# RCShield-arm-v0.net
KiCad netlist of a schematic drawn in EAGLE
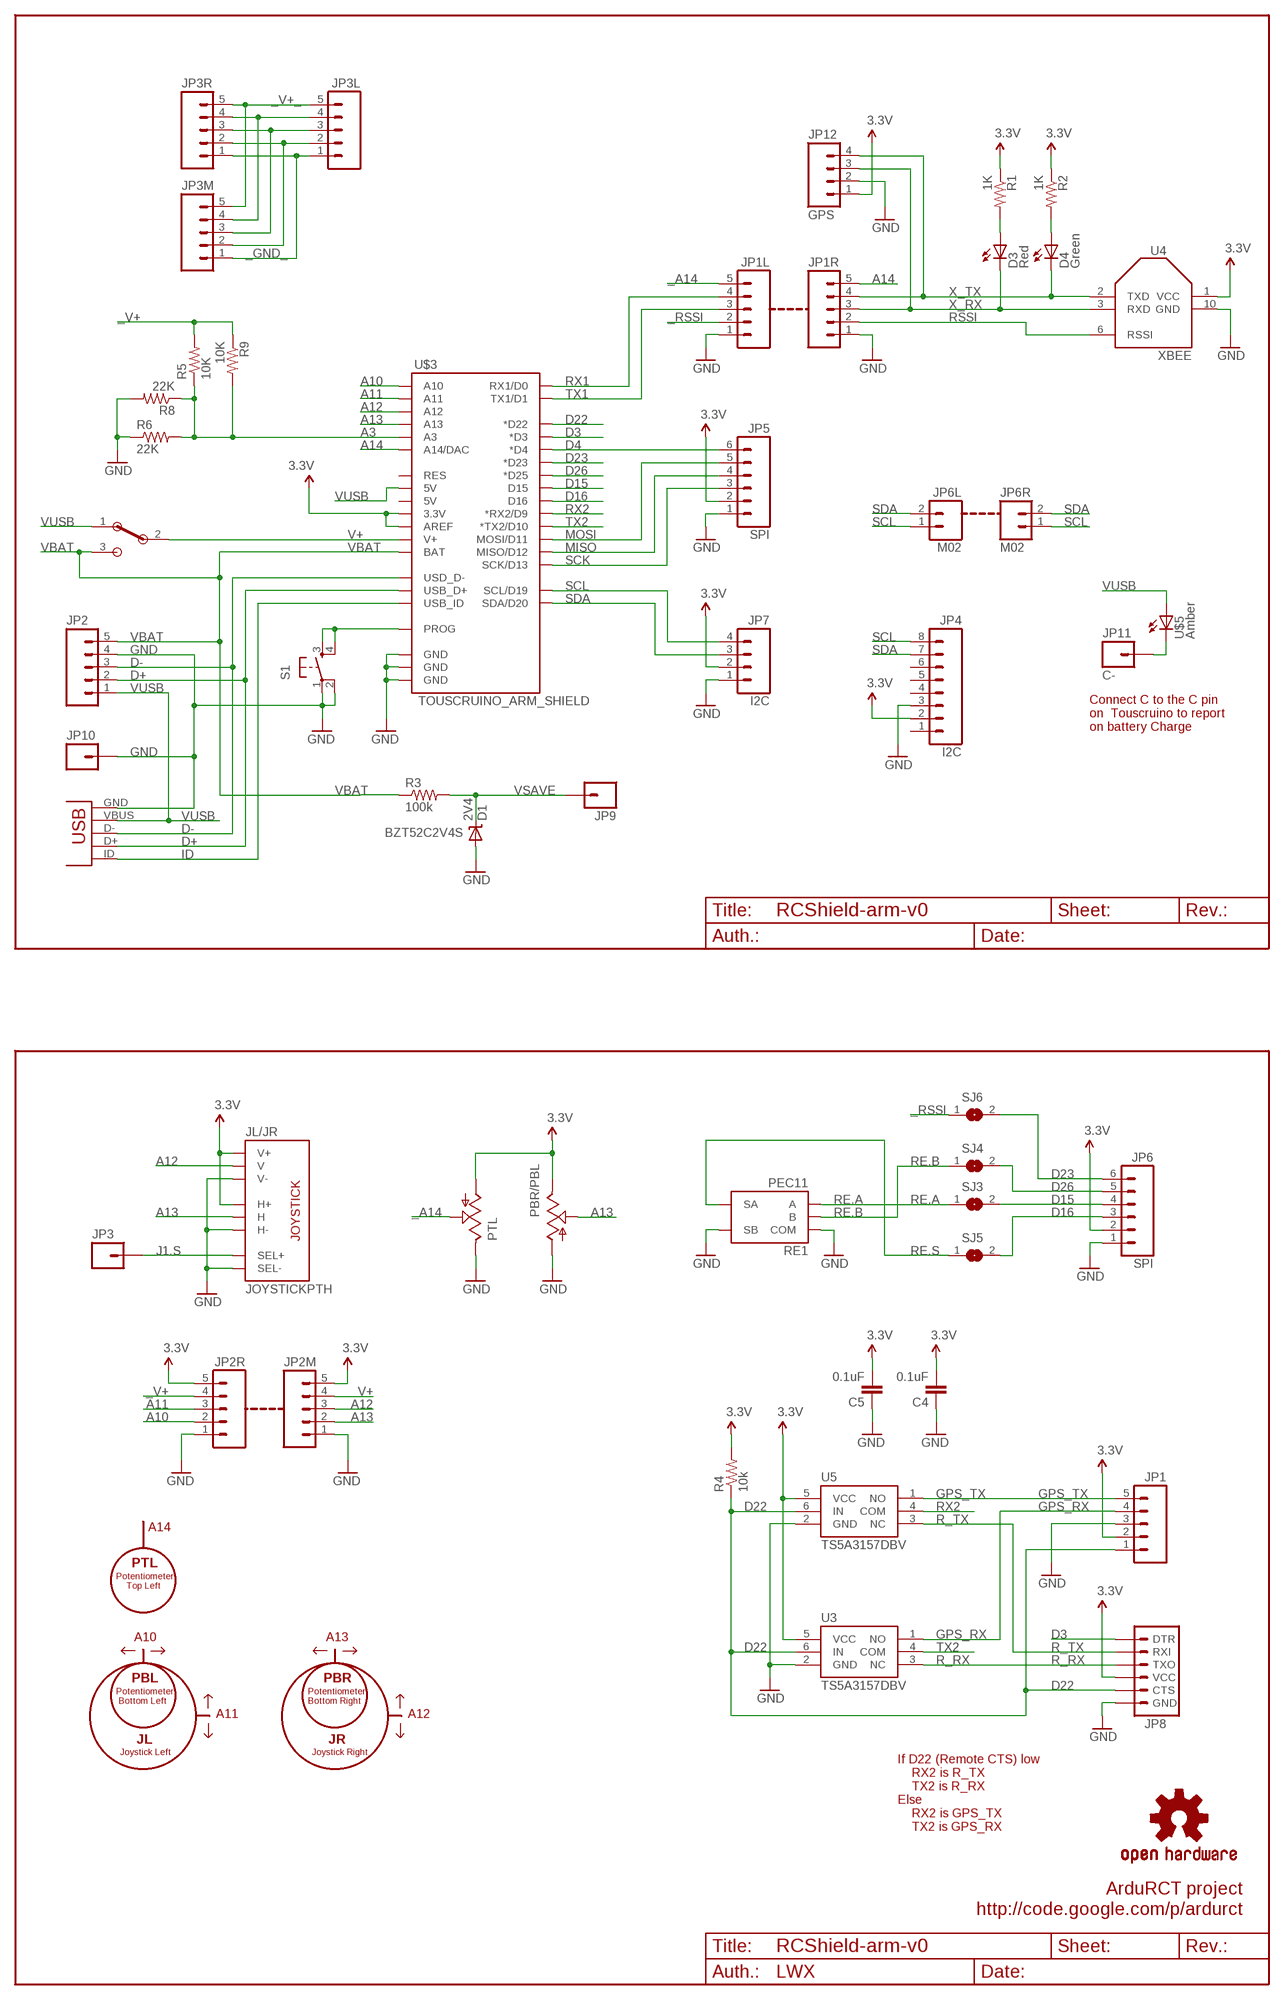
[diagram p0: schematic, sheet 1]

(export (version "E")
  (design (tool "Eeschema 10.0.6"))
  (components
    (comp (ref "C4")
      (value "0.1uF")
      (footprint "eagle-import:0805")
      (libsource (lib "eagle-import") (part "CAP0805"))
    )
    (comp (ref "C5")
      (value "0.1uF")
      (footprint "eagle-import:0805")
      (libsource (lib "eagle-import") (part "CAP0805"))
    )
    (comp (ref "D1")
      (value "2V4")
      (footprint "eagle-import:SOD-323")
      (libsource (lib "eagle-import") (part "DIODE-ZENER-BZT52"))
    )
    (comp (ref "D3")
      (value "Red")
      (footprint "eagle-import:LED")
      (libsource (lib "eagle-import") (part "LED"))
    )
    (comp (ref "D4")
      (value "Green")
      (footprint "eagle-import:LED")
      (libsource (lib "eagle-import") (part "LED"))
    )
    (comp (ref "JL/JR")
      (value "JOYSTICKPTH")
      (footprint "eagle-import:JOYSTICK")
      (libsource (lib "eagle-import") (part "JOYSTICKPTH"))
    )
    (comp (ref "JP1")
      (value "M05PTH")
      (footprint "eagle-import:1X05")
      (libsource (lib "eagle-import") (part "M05PTH"))
    )
    (comp (ref "JP1L")
      (value "M05")
      (footprint "eagle-import:2+3")
      (libsource (lib "eagle-import") (part "M05"))
    )
    (comp (ref "JP1R")
      (value "M05")
      (footprint "eagle-import:2+3")
      (libsource (lib "eagle-import") (part "M05"))
    )
    (comp (ref "JP2")
      (value "M05PTH")
      (footprint "eagle-import:1X05")
      (libsource (lib "eagle-import") (part "M05PTH"))
    )
    (comp (ref "JP2M")
      (value "M05")
      (footprint "eagle-import:2+3")
      (libsource (lib "eagle-import") (part "M05"))
    )
    (comp (ref "JP2R")
      (value "M05")
      (footprint "eagle-import:2+3")
      (libsource (lib "eagle-import") (part "M05"))
    )
    (comp (ref "JP3")
      (value "M01PTH")
      (footprint "eagle-import:1X01")
      (libsource (lib "eagle-import") (part "M01PTH"))
    )
    (comp (ref "JP3L")
      (value "M05")
      (footprint "eagle-import:2+3")
      (libsource (lib "eagle-import") (part "M05"))
    )
    (comp (ref "JP3M")
      (value "M05")
      (footprint "eagle-import:2+3")
      (libsource (lib "eagle-import") (part "M05"))
    )
    (comp (ref "JP3R")
      (value "M05")
      (footprint "eagle-import:2+3")
      (libsource (lib "eagle-import") (part "M05"))
    )
    (comp (ref "JP4")
      (value "I2C")
      (footprint "eagle-import:1X08")
      (libsource (lib "eagle-import") (part "M08"))
    )
    (comp (ref "JP5")
      (value "SPI")
      (footprint "eagle-import:1X06")
      (libsource (lib "eagle-import") (part "M06SIP"))
    )
    (comp (ref "JP6")
      (value "SPI")
      (footprint "eagle-import:1X06")
      (libsource (lib "eagle-import") (part "M06SIP"))
    )
    (comp (ref "JP6L")
      (value "M02")
      (footprint "eagle-import:1X02")
      (libsource (lib "eagle-import") (part "M02"))
    )
    (comp (ref "JP6R")
      (value "M02")
      (footprint "eagle-import:1X02")
      (libsource (lib "eagle-import") (part "M02"))
    )
    (comp (ref "JP7")
      (value "I2C")
      (footprint "eagle-import:1X04")
      (libsource (lib "eagle-import") (part "M04"))
    )
    (comp (ref "JP8")
      (value "ARDUINO_SERIAL_PROGRAM")
      (footprint "eagle-import:1X06_F")
      (libsource (lib "eagle-import") (part "ARDUINO_SERIAL_PROGRAM"))
    )
    (comp (ref "JP9")
      (value "M01PTH")
      (footprint "eagle-import:1X01")
      (libsource (lib "eagle-import") (part "M01PTH"))
    )
    (comp (ref "JP10")
      (value "M01PTH")
      (footprint "eagle-import:1X01")
      (libsource (lib "eagle-import") (part "M01PTH"))
    )
    (comp (ref "JP11")
      (value "C-")
      (footprint "eagle-import:1X01")
      (libsource (lib "eagle-import") (part "M01PTH"))
    )
    (comp (ref "JP12")
      (value "GPS")
      (footprint "eagle-import:1X04")
      (libsource (lib "eagle-import") (part "M04"))
    )
    (comp (ref "PBR/PBL")
      (value "POT")
      (footprint "eagle-import:ALPS_POT")
      (libsource (lib "eagle-import") (part "POT"))
    )
    (comp (ref "PTL")
      (value "POT")
      (footprint "eagle-import:ALPS_POT")
      (libsource (lib "eagle-import") (part "POT"))
    )
    (comp (ref "R1")
      (value "1K")
      (footprint "eagle-import:0805")
      (libsource (lib "eagle-import") (part "RESISTOR0805-RES"))
    )
    (comp (ref "R2")
      (value "1K")
      (footprint "eagle-import:0805")
      (libsource (lib "eagle-import") (part "RESISTOR0805-RES"))
    )
    (comp (ref "R3")
      (value "100k")
      (footprint "eagle-import:0805")
      (libsource (lib "eagle-import") (part "RESISTOR0805-RES"))
    )
    (comp (ref "R4")
      (value "10k")
      (footprint "eagle-import:0805")
      (libsource (lib "eagle-import") (part "RESISTOR0805-RES"))
    )
    (comp (ref "R5")
      (value "10K")
      (footprint "eagle-import:0805")
      (libsource (lib "eagle-import") (part "RESISTOR0805-RES"))
    )
    (comp (ref "R6")
      (value "22K")
      (footprint "eagle-import:0805")
      (libsource (lib "eagle-import") (part "RESISTOR0805-RES"))
    )
    (comp (ref "R8")
      (value "22K")
      (footprint "eagle-import:0207_7")
      (libsource (lib "eagle-import") (part "R-US_0207/7"))
    )
    (comp (ref "R9")
      (value "10K")
      (footprint "eagle-import:0207_7")
      (libsource (lib "eagle-import") (part "R-US_0207/7"))
    )
    (comp (ref "RE1")
      (value "PEC11")
      (footprint "eagle-import:PEC11")
      (libsource (lib "eagle-import") (part "PEC11"))
    )
    (comp (ref "S1")
      (value "TAC_SWITCHPTH")
      (footprint "eagle-import:TACTILE-PTH")
      (libsource (lib "eagle-import") (part "TAC_SWITCHPTH"))
    )
    (comp (ref "S4")
      (value "EG1224")
      (footprint "eagle-import:EG1224")
      (libsource (lib "eagle-import") (part "EG1224"))
    )
    (comp (ref "SJ3") (value "SJ") (footprint "eagle-import:SJ") (libsource (lib "eagle-import") (part "SJ")))
    (comp (ref "SJ4") (value "SJ") (footprint "eagle-import:SJ") (libsource (lib "eagle-import") (part "SJ")))
    (comp (ref "SJ5") (value "SJ") (footprint "eagle-import:SJ") (libsource (lib "eagle-import") (part "SJ")))
    (comp (ref "SJ6") (value "SJ") (footprint "eagle-import:SJ") (libsource (lib "eagle-import") (part "SJ")))
    (comp (ref "U$1")
      (value "OSHW-LOGOM")
      (footprint "eagle-import:OSHW-LOGO-M")
      (libsource (lib "eagle-import") (part "OSHW-LOGOM"))
    )
    (comp (ref "U$3")
      (value "TOUSCRUINO_ARM_SHIELD")
      (footprint "eagle-import:TOUSCRUINO_ARM_SHIELD_SPLIT")
      (libsource (lib "eagle-import") (part "TOUSCRUINO_ARM_SHIELD"))
    )
    (comp (ref "U$5")
      (value "Amber")
      (footprint "eagle-import:LED")
      (libsource (lib "eagle-import") (part "LED"))
    )
    (comp (ref "U3")
      (value "TS5A3157DBV")
      (footprint "eagle-import:SOT23-6")
      (libsource (lib "eagle-import") (part "TS5A3157DBV"))
    )
    (comp (ref "U4")
      (value "XBEE")
      (footprint "eagle-import:XBEE-SMD")
      (libsource (lib "eagle-import") (part "XBEE-RSSI"))
    )
    (comp (ref "U5")
      (value "TS5A3157DBV")
      (footprint "eagle-import:SOT23-6")
      (libsource (lib "eagle-import") (part "TS5A3157DBV"))
    )
    (comp (ref "X1")
      (value "USB")
      (footprint "eagle-import:USB-MICROB")
      (libsource (lib "eagle-import") (part "USB"))
    )
  )
  (nets
    (net (code "1") (name "/A3") (class "Default")
      (node (ref "R5") (pin "1") (pinfunction "1_1") (pintype "passive"))
      (node (ref "R6") (pin "2") (pinfunction "2_2") (pintype "passive"))
      (node (ref "R8") (pin "1") (pinfunction "1_1") (pintype "passive"))
      (node (ref "R9") (pin "2") (pinfunction "2_2") (pintype "passive"))
      (node (ref "U$3") (pin "A3") (pinfunction "A3_A3") (pintype "bidirectional"))
    )
    (net (code "2") (name "/A10") (class "Default")
      (node (ref "JP2R") (pin "2") (pinfunction "2_2") (pintype "passive"))
      (node (ref "U$3") (pin "A10") (pinfunction "A10_A10") (pintype "bidirectional"))
    )
    (net (code "3") (name "/A11") (class "Default")
      (node (ref "JP2R") (pin "3") (pinfunction "3_3") (pintype "passive"))
      (node (ref "U$3") (pin "A11") (pinfunction "A11_A11") (pintype "bidirectional"))
    )
    (net (code "4") (name "/A12") (class "Default")
      (node (ref "JL/JR") (pin "V2") (pinfunction "V_V2") (pintype "bidirectional"))
      (node (ref "JP2M") (pin "3") (pinfunction "3_3") (pintype "passive"))
      (node (ref "U$3") (pin "A12") (pinfunction "A12_A12") (pintype "bidirectional"))
    )
    (net (code "5") (name "/A13") (class "Default")
      (node (ref "JL/JR") (pin "H2") (pinfunction "H_H2") (pintype "bidirectional"))
      (node (ref "JP2M") (pin "2") (pinfunction "2_2") (pintype "passive"))
      (node (ref "PBR/PBL") (pin "P$2") (pinfunction "S_P$2") (pintype "passive"))
      (node (ref "U$3") (pin "A13") (pinfunction "A13_A13") (pintype "bidirectional"))
    )
    (net (code "6") (name "/A14") (class "Default")
      (node (ref "JP1R") (pin "5") (pinfunction "5_5") (pintype "passive"))
      (node (ref "U$3") (pin "A14") (pinfunction "A14/DAC_A14") (pintype "bidirectional"))
    )
    (net (code "7") (name "/D+") (class "Default")
      (node (ref "JP2") (pin "2") (pinfunction "2_2") (pintype "passive"))
      (node (ref "U$3") (pin "USB_D+") (pinfunction "USB_D+_USB_D+") (pintype "bidirectional"))
      (node (ref "X1") (pin "D+") (pinfunction "D+_D+") (pintype "bidirectional"))
    )
    (net (code "8") (name "/D-") (class "Default")
      (node (ref "JP2") (pin "3") (pinfunction "3_3") (pintype "passive"))
      (node (ref "U$3") (pin "USB_D-") (pinfunction "USD_D-_USB_D-") (pintype "bidirectional"))
      (node (ref "X1") (pin "D-") (pinfunction "D-_D-") (pintype "bidirectional"))
    )
    (net (code "9") (name "/D3") (class "Default")
      (node (ref "JP8") (pin "1") (pinfunction "DTR_1") (pintype "passive"))
      (node (ref "U$3") (pin "D3") (pinfunction "*D3_D3") (pintype "bidirectional"))
    )
    (net (code "10") (name "/D4") (class "Default")
      (node (ref "JP5") (pin "6") (pinfunction "6_6") (pintype "passive"))
      (node (ref "U$3") (pin "D4") (pinfunction "*D4_D4") (pintype "bidirectional"))
    )
    (net (code "11") (name "/D15") (class "Default")
      (node (ref "JP6") (pin "4") (pinfunction "4_4") (pintype "passive"))
      (node (ref "SJ3") (pin "2") (pinfunction "2_2") (pintype "passive"))
      (node (ref "U$3") (pin "D15") (pinfunction "D15_D15") (pintype "bidirectional"))
    )
    (net (code "12") (name "/D16") (class "Default")
      (node (ref "JP6") (pin "3") (pinfunction "3_3") (pintype "passive"))
      (node (ref "SJ5") (pin "2") (pinfunction "2_2") (pintype "passive"))
      (node (ref "U$3") (pin "D16") (pinfunction "D16_D16") (pintype "bidirectional"))
    )
    (net (code "13") (name "/D22") (class "Default")
      (node (ref "JP1") (pin "1") (pinfunction "1_1") (pintype "passive"))
      (node (ref "JP8") (pin "5") (pinfunction "CTS_5") (pintype "passive"))
      (node (ref "R4") (pin "1") (pinfunction "1_1") (pintype "passive"))
      (node (ref "U$3") (pin "D22") (pinfunction "*D22_D22") (pintype "bidirectional"))
      (node (ref "U3") (pin "6") (pinfunction "IN_6") (pintype "bidirectional"))
      (node (ref "U5") (pin "6") (pinfunction "IN_6") (pintype "bidirectional"))
    )
    (net (code "14") (name "/D23") (class "Default")
      (node (ref "JP6") (pin "6") (pinfunction "6_6") (pintype "passive"))
      (node (ref "SJ6") (pin "2") (pinfunction "2_2") (pintype "passive"))
      (node (ref "U$3") (pin "D23") (pinfunction "*D23_D23") (pintype "bidirectional"))
    )
    (net (code "15") (name "/D26") (class "Default")
      (node (ref "JP6") (pin "5") (pinfunction "5_5") (pintype "passive"))
      (node (ref "SJ4") (pin "2") (pinfunction "2_2") (pintype "passive"))
      (node (ref "U$3") (pin "D25") (pinfunction "*D25_D25") (pintype "bidirectional"))
    )
    (net (code "16") (name "/GPS_RX") (class "Default")
      (node (ref "JP1") (pin "4") (pinfunction "4_4") (pintype "passive"))
      (node (ref "U3") (pin "1") (pinfunction "NO_1") (pintype "bidirectional"))
    )
    (net (code "17") (name "/GPS_TX") (class "Default")
      (node (ref "JP1") (pin "5") (pinfunction "5_5") (pintype "passive"))
      (node (ref "U5") (pin "1") (pinfunction "NO_1") (pintype "bidirectional"))
    )
    (net (code "18") (name "/ID") (class "Default")
      (node (ref "U$3") (pin "USB_ID") (pinfunction "USB_ID_USB_ID") (pintype "bidirectional"))
      (node (ref "X1") (pin "ID") (pinfunction "ID_ID") (pintype "bidirectional"))
    )
    (net (code "19") (name "/J1.S") (class "Default")
      (node (ref "JL/JR") (pin "B1A") (pinfunction "SEL+_B1A") (pintype "bidirectional"))
      (node (ref "JP3") (pin "1") (pinfunction "1_1") (pintype "passive"))
    )
    (net (code "20") (name "/MISO") (class "Default")
      (node (ref "JP5") (pin "4") (pinfunction "4_4") (pintype "passive"))
      (node (ref "U$3") (pin "D12") (pinfunction "MISO/D12_D12") (pintype "bidirectional"))
    )
    (net (code "21") (name "/MOSI") (class "Default")
      (node (ref "JP5") (pin "5") (pinfunction "5_5") (pintype "passive"))
      (node (ref "U$3") (pin "D11") (pinfunction "MOSI/D11_D11") (pintype "bidirectional"))
    )
    (net (code "22") (name "/RE.A") (class "Default")
      (node (ref "RE1") (pin "A") (pinfunction "A_A") (pintype "bidirectional"))
      (node (ref "SJ3") (pin "1") (pinfunction "1_1") (pintype "passive"))
    )
    (net (code "23") (name "/RE.B") (class "Default")
      (node (ref "RE1") (pin "B") (pinfunction "B_B") (pintype "bidirectional"))
      (node (ref "SJ4") (pin "1") (pinfunction "1_1") (pintype "passive"))
    )
    (net (code "24") (name "/RE.S") (class "Default")
      (node (ref "RE1") (pin "S1") (pinfunction "SA_S1") (pintype "bidirectional"))
      (node (ref "SJ5") (pin "1") (pinfunction "1_1") (pintype "passive"))
    )
    (net (code "25") (name "/RSSI") (class "Default")
      (node (ref "JP1R") (pin "2") (pinfunction "2_2") (pintype "passive"))
      (node (ref "U4") (pin "6") (pinfunction "RSSI_6") (pintype "bidirectional"))
    )
    (net (code "26") (name "/RX1") (class "Default")
      (node (ref "JP1L") (pin "4") (pinfunction "4_4") (pintype "passive"))
      (node (ref "U$3") (pin "RX1/D0") (pinfunction "RX1/D0_RX1/D0") (pintype "bidirectional"))
    )
    (net (code "27") (name "/RX2") (class "Default")
      (node (ref "U$3") (pin "D9") (pinfunction "*RX2/D9_D9") (pintype "bidirectional"))
      (node (ref "U5") (pin "4") (pinfunction "COM_4") (pintype "bidirectional"))
    )
    (net (code "28") (name "/R_RX") (class "Default")
      (node (ref "JP8") (pin "3") (pinfunction "TXO_3") (pintype "passive"))
      (node (ref "U3") (pin "3") (pinfunction "NC_3") (pintype "bidirectional"))
    )
    (net (code "29") (name "/R_TX") (class "Default")
      (node (ref "JP8") (pin "2") (pinfunction "RXI_2") (pintype "passive"))
      (node (ref "U5") (pin "3") (pinfunction "NC_3") (pintype "bidirectional"))
    )
    (net (code "30") (name "/SCK") (class "Default")
      (node (ref "JP5") (pin "3") (pinfunction "3_3") (pintype "passive"))
      (node (ref "U$3") (pin "D13") (pinfunction "SCK/D13_D13") (pintype "bidirectional"))
    )
    (net (code "31") (name "/SCL") (class "Default")
      (node (ref "JP4") (pin "8") (pinfunction "8_8") (pintype "passive"))
      (node (ref "JP6L") (pin "1") (pinfunction "1_1") (pintype "passive"))
      (node (ref "JP6R") (pin "1") (pinfunction "1_1") (pintype "passive"))
      (node (ref "JP7") (pin "4") (pinfunction "4_4") (pintype "passive"))
      (node (ref "U$3") (pin "SCL") (pinfunction "SCL/D19_SCL") (pintype "bidirectional"))
    )
    (net (code "32") (name "/SDA") (class "Default")
      (node (ref "JP4") (pin "7") (pinfunction "7_7") (pintype "passive"))
      (node (ref "JP6L") (pin "2") (pinfunction "2_2") (pintype "passive"))
      (node (ref "JP6R") (pin "2") (pinfunction "2_2") (pintype "passive"))
      (node (ref "JP7") (pin "3") (pinfunction "3_3") (pintype "passive"))
      (node (ref "U$3") (pin "SDA") (pinfunction "SDA/D20_SDA") (pintype "bidirectional"))
    )
    (net (code "33") (name "/TX1") (class "Default")
      (node (ref "JP1L") (pin "3") (pinfunction "3_3") (pintype "passive"))
      (node (ref "U$3") (pin "TX1/D1") (pinfunction "TX1/D1_TX1/D1") (pintype "bidirectional"))
    )
    (net (code "34") (name "/TX2") (class "Default")
      (node (ref "U$3") (pin "D10") (pinfunction "*TX2/D10_D10") (pintype "bidirectional"))
      (node (ref "U3") (pin "4") (pinfunction "COM_4") (pintype "bidirectional"))
    )
    (net (code "35") (name "/V+") (class "Default")
      (node (ref "JP2M") (pin "4") (pinfunction "4_4") (pintype "passive"))
      (node (ref "S4") (pin "2") (pinfunction "2_2") (pintype "bidirectional"))
      (node (ref "U$3") (pin "V+") (pinfunction "V+_V+") (pintype "bidirectional"))
    )
    (net (code "36") (name "/VBAT") (class "Default")
      (node (ref "JP2") (pin "5") (pinfunction "5_5") (pintype "passive"))
      (node (ref "R3") (pin "1") (pinfunction "1_1") (pintype "passive"))
      (node (ref "S4") (pin "3") (pinfunction "3_3") (pintype "bidirectional"))
      (node (ref "U$3") (pin "BAT") (pinfunction "BAT_BAT") (pintype "bidirectional"))
    )
    (net (code "37") (name "/VSAVE") (class "Default")
      (node (ref "D1") (pin "1") (pinfunction "C_1") (pintype "passive"))
      (node (ref "JP9") (pin "1") (pinfunction "1_1") (pintype "passive"))
      (node (ref "R3") (pin "2") (pinfunction "2_2") (pintype "passive"))
    )
    (net (code "38") (name "/VUSB") (class "Default")
      (node (ref "JP2") (pin "1") (pinfunction "1_1") (pintype "passive"))
      (node (ref "S4") (pin "1") (pinfunction "1_1") (pintype "bidirectional"))
      (node (ref "U$3") (pin "5V@1") (pinfunction "5V_5V@1") (pintype "bidirectional"))
      (node (ref "U$5") (pin "A1") (pinfunction "A_A1") (pintype "passive"))
      (node (ref "X1") (pin "VBUS") (pinfunction "VBUS_VBUS") (pintype "bidirectional"))
    )
    (net (code "39") (name "/X_RX") (class "Default")
      (node (ref "D3") (pin "C1") (pinfunction "C_C1") (pintype "passive"))
      (node (ref "JP12") (pin "3") (pinfunction "3_3") (pintype "passive"))
      (node (ref "JP1R") (pin "3") (pinfunction "3_3") (pintype "passive"))
      (node (ref "U4") (pin "3") (pinfunction "RXD_3") (pintype "bidirectional"))
    )
    (net (code "40") (name "/X_TX") (class "Default")
      (node (ref "D4") (pin "C1") (pinfunction "C_C1") (pintype "passive"))
      (node (ref "JP12") (pin "4") (pinfunction "4_4") (pintype "passive"))
      (node (ref "JP1R") (pin "4") (pinfunction "4_4") (pintype "passive"))
      (node (ref "U4") (pin "2") (pinfunction "TXD_2") (pintype "bidirectional"))
    )
    (net (code "41") (name "/_A14") (class "Default")
      (node (ref "JP1L") (pin "5") (pinfunction "5_5") (pintype "passive"))
      (node (ref "PTL") (pin "P$2") (pinfunction "S_P$2") (pintype "passive"))
    )
    (net (code "42") (name "/_GND_") (class "Default")
      (node (ref "JP3L") (pin "1") (pinfunction "1_1") (pintype "passive"))
      (node (ref "JP3M") (pin "1") (pinfunction "1_1") (pintype "passive"))
      (node (ref "JP3R") (pin "1") (pinfunction "1_1") (pintype "passive"))
    )
    (net (code "43") (name "/_RSSI") (class "Default")
      (node (ref "JP1L") (pin "2") (pinfunction "2_2") (pintype "passive"))
      (node (ref "SJ6") (pin "1") (pinfunction "1_1") (pintype "passive"))
    )
    (net (code "44") (name "/_V+") (class "Default")
      (node (ref "JP2R") (pin "4") (pinfunction "4_4") (pintype "passive"))
      (node (ref "R5") (pin "2") (pinfunction "2_2") (pintype "passive"))
      (node (ref "R9") (pin "1") (pinfunction "1_1") (pintype "passive"))
    )
    (net (code "45") (name "/_V+_") (class "Default")
      (node (ref "JP3L") (pin "5") (pinfunction "5_5") (pintype "passive"))
      (node (ref "JP3M") (pin "5") (pinfunction "5_5") (pintype "passive"))
      (node (ref "JP3R") (pin "5") (pinfunction "5_5") (pintype "passive"))
    )
    (net (code "46") (name "3.3V") (class "Default")
      (node (ref "C4") (pin "2") (pinfunction "2_2") (pintype "passive"))
      (node (ref "C5") (pin "2") (pinfunction "2_2") (pintype "passive"))
      (node (ref "JL/JR") (pin "H1") (pinfunction "H+_H1") (pintype "bidirectional"))
      (node (ref "JL/JR") (pin "V1") (pinfunction "V+_V1") (pintype "bidirectional"))
      (node (ref "JP1") (pin "2") (pinfunction "2_2") (pintype "passive"))
      (node (ref "JP12") (pin "1") (pinfunction "1_1") (pintype "passive"))
      (node (ref "JP2M") (pin "5") (pinfunction "5_5") (pintype "passive"))
      (node (ref "JP2R") (pin "5") (pinfunction "5_5") (pintype "passive"))
      (node (ref "JP4") (pin "2") (pinfunction "2_2") (pintype "passive"))
      (node (ref "JP5") (pin "2") (pinfunction "2_2") (pintype "passive"))
      (node (ref "JP6") (pin "2") (pinfunction "2_2") (pintype "passive"))
      (node (ref "JP7") (pin "2") (pinfunction "2_2") (pintype "passive"))
      (node (ref "JP8") (pin "4") (pinfunction "VCC_4") (pintype "passive"))
      (node (ref "PBR/PBL") (pin "P$1") (pinfunction "E_P$1") (pintype "passive"))
      (node (ref "PTL") (pin "P$3") (pinfunction "A_P$3") (pintype "passive"))
      (node (ref "R1") (pin "1") (pinfunction "1_1") (pintype "passive"))
      (node (ref "R2") (pin "1") (pinfunction "1_1") (pintype "passive"))
      (node (ref "R4") (pin "2") (pinfunction "2_2") (pintype "passive"))
      (node (ref "U$3") (pin "3.3V") (pinfunction "3.3V_3.3V") (pintype "bidirectional"))
      (node (ref "U$3") (pin "AREF") (pinfunction "AREF_AREF") (pintype "bidirectional"))
      (node (ref "U3") (pin "5") (pinfunction "VCC_5") (pintype "bidirectional"))
      (node (ref "U4") (pin "1") (pinfunction "VCC_1") (pintype "bidirectional"))
      (node (ref "U5") (pin "5") (pinfunction "VCC_5") (pintype "bidirectional"))
    )
    (net (code "47") (name "GND") (class "Default")
      (node (ref "C4") (pin "1") (pinfunction "1_1") (pintype "passive"))
      (node (ref "C5") (pin "1") (pinfunction "1_1") (pintype "passive"))
      (node (ref "D1") (pin "2") (pinfunction "A_2") (pintype "passive"))
      (node (ref "JL/JR") (pin "B2A") (pinfunction "SEL-_B2A") (pintype "bidirectional"))
      (node (ref "JL/JR") (pin "H3") (pinfunction "H-_H3") (pintype "bidirectional"))
      (node (ref "JL/JR") (pin "V3") (pinfunction "V-_V3") (pintype "bidirectional"))
      (node (ref "JP1") (pin "3") (pinfunction "3_3") (pintype "passive"))
      (node (ref "JP10") (pin "1") (pinfunction "1_1") (pintype "passive"))
      (node (ref "JP12") (pin "2") (pinfunction "2_2") (pintype "passive"))
      (node (ref "JP1L") (pin "1") (pinfunction "1_1") (pintype "passive"))
      (node (ref "JP1R") (pin "1") (pinfunction "1_1") (pintype "passive"))
      (node (ref "JP2") (pin "4") (pinfunction "4_4") (pintype "passive"))
      (node (ref "JP2M") (pin "1") (pinfunction "1_1") (pintype "passive"))
      (node (ref "JP2R") (pin "1") (pinfunction "1_1") (pintype "passive"))
      (node (ref "JP4") (pin "3") (pinfunction "3_3") (pintype "passive"))
      (node (ref "JP5") (pin "1") (pinfunction "1_1") (pintype "passive"))
      (node (ref "JP6") (pin "1") (pinfunction "1_1") (pintype "passive"))
      (node (ref "JP7") (pin "1") (pinfunction "1_1") (pintype "passive"))
      (node (ref "JP8") (pin "6") (pinfunction "GND_6") (pintype "passive"))
      (node (ref "PBR/PBL") (pin "P$3") (pinfunction "A_P$3") (pintype "passive"))
      (node (ref "PTL") (pin "P$1") (pinfunction "E_P$1") (pintype "passive"))
      (node (ref "R6") (pin "1") (pinfunction "1_1") (pintype "passive"))
      (node (ref "R8") (pin "2") (pinfunction "2_2") (pintype "passive"))
      (node (ref "RE1") (pin "C") (pinfunction "COM_C") (pintype "bidirectional"))
      (node (ref "RE1") (pin "S2") (pinfunction "SB_S2") (pintype "bidirectional"))
      (node (ref "S1") (pin "1") (pinfunction "1_1") (pintype "passive"))
      (node (ref "S1") (pin "2") (pinfunction "2_2") (pintype "passive"))
      (node (ref "U$3") (pin "GND@0") (pinfunction "GND_GND@0") (pintype "bidirectional"))
      (node (ref "U$3") (pin "GND@1") (pinfunction "GND_GND@1") (pintype "bidirectional"))
      (node (ref "U$3") (pin "GND@2") (pinfunction "GND_GND@2") (pintype "bidirectional"))
      (node (ref "U3") (pin "2") (pinfunction "GND_2") (pintype "bidirectional"))
      (node (ref "U4") (pin "10") (pinfunction "GND_10") (pintype "bidirectional"))
      (node (ref "U5") (pin "2") (pinfunction "GND_2") (pintype "bidirectional"))
      (node (ref "X1") (pin "GND") (pinfunction "GND_GND") (pintype "bidirectional"))
    )
    (net (code "48") (name "Net-(D3-A)") (class "Default")
      (node (ref "D3") (pin "A1") (pinfunction "A_A1") (pintype "passive"))
      (node (ref "R1") (pin "2") (pinfunction "2_2") (pintype "passive"))
    )
    (net (code "49") (name "Net-(D4-A)") (class "Default")
      (node (ref "D4") (pin "A1") (pinfunction "A_A1") (pintype "passive"))
      (node (ref "R2") (pin "2") (pinfunction "2_2") (pintype "passive"))
    )
    (net (code "50") (name "Net-(JP3L-Pad2)") (class "Default")
      (node (ref "JP3L") (pin "2") (pinfunction "2_2") (pintype "passive"))
      (node (ref "JP3M") (pin "2") (pinfunction "2_2") (pintype "passive"))
      (node (ref "JP3R") (pin "2") (pinfunction "2_2") (pintype "passive"))
    )
    (net (code "51") (name "Net-(JP3L-Pad3)") (class "Default")
      (node (ref "JP3L") (pin "3") (pinfunction "3_3") (pintype "passive"))
      (node (ref "JP3M") (pin "3") (pinfunction "3_3") (pintype "passive"))
      (node (ref "JP3R") (pin "3") (pinfunction "3_3") (pintype "passive"))
    )
    (net (code "52") (name "Net-(JP3L-Pad4)") (class "Default")
      (node (ref "JP3L") (pin "4") (pinfunction "4_4") (pintype "passive"))
      (node (ref "JP3M") (pin "4") (pinfunction "4_4") (pintype "passive"))
      (node (ref "JP3R") (pin "4") (pinfunction "4_4") (pintype "passive"))
    )
    (net (code "53") (name "Net-(S1-Pad3)") (class "Default")
      (node (ref "S1") (pin "3") (pinfunction "3_3") (pintype "passive"))
      (node (ref "S1") (pin "4") (pinfunction "4_4") (pintype "passive"))
      (node (ref "U$3") (pin "PROG") (pinfunction "PROG_PROG") (pintype "bidirectional"))
    )
    (net (code "54") (name "Net-(U$5-C)") (class "Default")
      (node (ref "JP11") (pin "1") (pinfunction "1_1") (pintype "passive"))
      (node (ref "U$5") (pin "C1") (pinfunction "C_C1") (pintype "passive"))
    )
    (net (code "55") (name "unconnected-(JP4-Pad1)") (class "Default")
      (node (ref "JP4") (pin "1") (pinfunction "1_1") (pintype "passive"))
    )
    (net (code "56") (name "unconnected-(JP4-Pad4)") (class "Default")
      (node (ref "JP4") (pin "4") (pinfunction "4_4") (pintype "passive"))
    )
    (net (code "57") (name "unconnected-(JP4-Pad5)") (class "Default")
      (node (ref "JP4") (pin "5") (pinfunction "5_5") (pintype "passive"))
    )
    (net (code "58") (name "unconnected-(JP4-Pad6)") (class "Default")
      (node (ref "JP4") (pin "6") (pinfunction "6_6") (pintype "passive"))
    )
    (net (code "59") (name "unconnected-(U$3-5V-Pad5V@0)") (class "Default")
      (node (ref "U$3") (pin "5V@0") (pinfunction "5V_5V@0") (pintype "bidirectional"))
    )
    (net (code "60") (name "unconnected-(U$3-PadRES)") (class "Default")
      (node (ref "U$3") (pin "RES") (pinfunction "RES_RES") (pintype "bidirectional"))
    )
  )
)
